# Micro_M3.net
KiCad netlist of a schematic drawn in Altium Designer
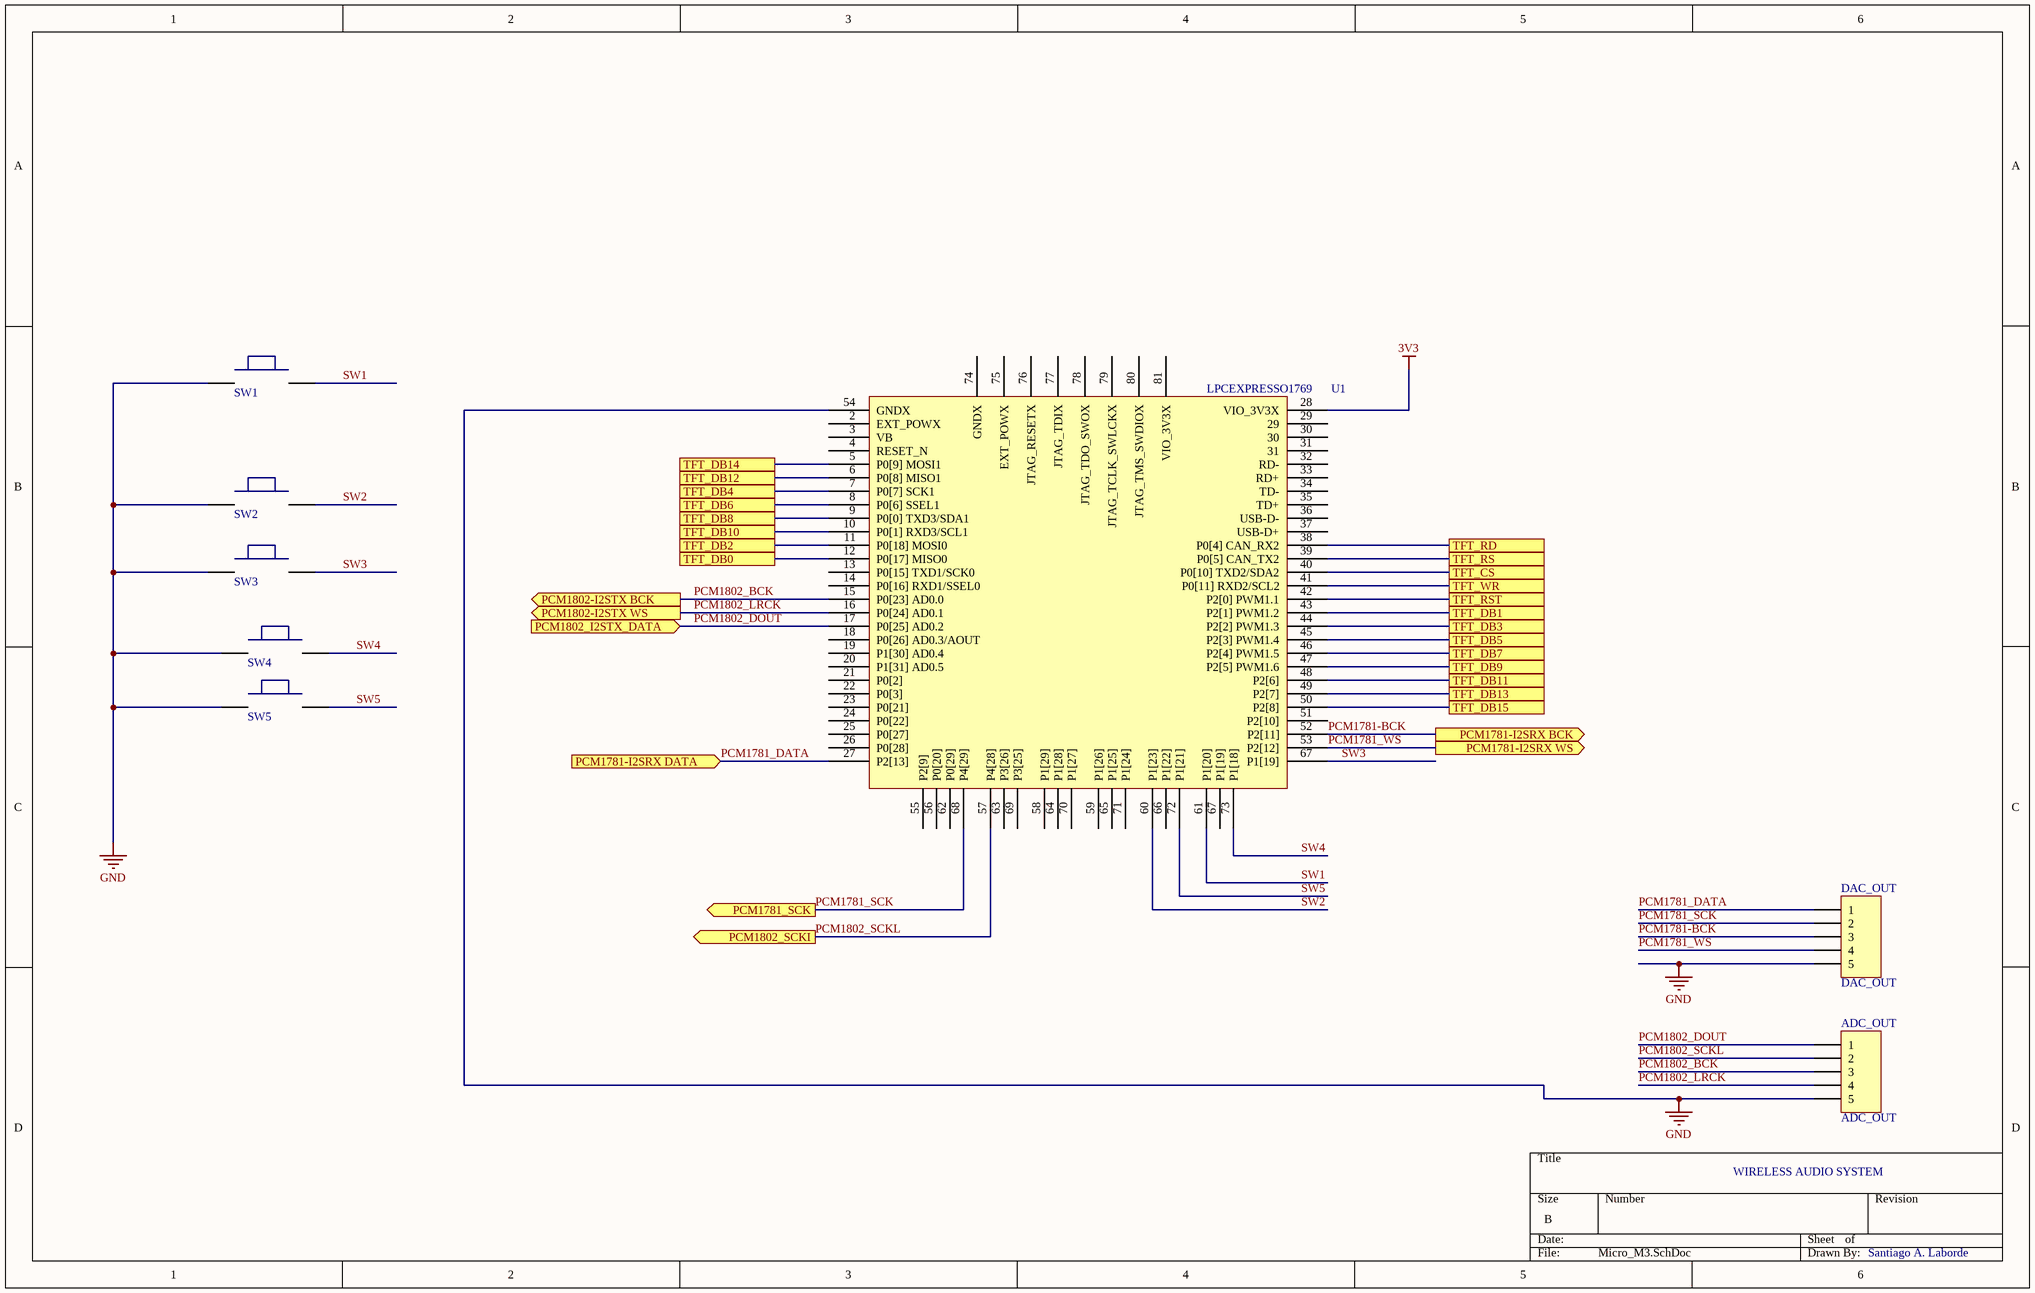
[diagram p0: Micro_M3.SchDoc]

(export (version "E")
  (design (tool "Eeschema 10.0.6"))
  (components
    (comp (ref "ADC_OUT")
      (value "ADC_OUT")
      (footprint "HDR1X5")
      (description "Header, 5-Pin")
      (fields (field (name "PUBLISHER") "Altium Limited"))
      (libsource (lib "Miscellaneous Connectors") (part "Header 5"))
    )
    (comp (ref "DAC_OUT")
      (value "DAC_OUT")
      (footprint "HDR1X5")
      (description "Header, 5-Pin")
      (fields (field (name "PUBLISHER") "Altium Limited"))
      (libsource (lib "Miscellaneous Connectors") (part "Header 5"))
    )
    (comp (ref "SW1")
      (value "PULSADOR")
      (footprint "Pulsador")
      (libsource (lib "TD2_Project") (part "PULSADOR"))
    )
    (comp (ref "SW2")
      (value "PULSADOR")
      (footprint "Pulsador")
      (libsource (lib "TD2_Project") (part "PULSADOR"))
    )
    (comp (ref "SW3")
      (value "PULSADOR")
      (footprint "Pulsador")
      (libsource (lib "TD2_Project") (part "PULSADOR"))
    )
    (comp (ref "SW4")
      (value "PULSADOR")
      (footprint "Pulsador")
      (libsource (lib "TD2_Project") (part "PULSADOR"))
    )
    (comp (ref "SW5")
      (value "PULSADOR")
      (footprint "SW_SMD(2)")
      (libsource (lib "TD2_Project") (part "PULSADOR"))
    )
    (comp (ref "U1")
      (value "LPCEXPRESSO1769")
      (footprint "LPCEXPRESSO1769")
      (libsource (lib "PCM") (part "LPCEXPRESSO1769"))
    )
  )
  (nets
    (net (code "1") (name "/PCM1781-BCK") (class "Default")
      (node (ref "DAC_OUT") (pin "3") (pinfunction "3_3") (pintype "passive"))
      (node (ref "U1") (pin "52") (pinfunction "P2[11]_52") (pintype "passive"))
    )
    (net (code "2") (name "/PCM1781_DATA") (class "Default")
      (node (ref "DAC_OUT") (pin "1") (pinfunction "1_1") (pintype "passive"))
      (node (ref "U1") (pin "27") (pinfunction "P2[13]_27") (pintype "passive"))
    )
    (net (code "3") (name "/PCM1781_SCK") (class "Default")
      (node (ref "DAC_OUT") (pin "2") (pinfunction "2_2") (pintype "passive"))
      (node (ref "U1") (pin "68") (pinfunction "P4[29]_68") (pintype "passive"))
    )
    (net (code "4") (name "/PCM1781_WS") (class "Default")
      (node (ref "DAC_OUT") (pin "4") (pinfunction "4_4") (pintype "passive"))
      (node (ref "U1") (pin "53") (pinfunction "P2[12]_53") (pintype "passive"))
    )
    (net (code "5") (name "/PCM1802_BCK") (class "Default")
      (node (ref "ADC_OUT") (pin "3") (pinfunction "3_3") (pintype "passive"))
      (node (ref "U1") (pin "15") (pinfunction "P0[23]_AD0.0_15") (pintype "passive"))
    )
    (net (code "6") (name "/PCM1802_DOUT") (class "Default")
      (node (ref "ADC_OUT") (pin "1") (pinfunction "1_1") (pintype "passive"))
      (node (ref "U1") (pin "17") (pinfunction "P0[25]_AD0.2_17") (pintype "passive"))
    )
    (net (code "7") (name "/PCM1802_LRCK") (class "Default")
      (node (ref "ADC_OUT") (pin "4") (pinfunction "4_4") (pintype "passive"))
      (node (ref "U1") (pin "16") (pinfunction "P0[24]_AD0.1_16") (pintype "passive"))
    )
    (net (code "8") (name "/PCM1802_SCKL") (class "Default")
      (node (ref "ADC_OUT") (pin "2") (pinfunction "2_2") (pintype "passive"))
      (node (ref "U1") (pin "57") (pinfunction "P4[28]_57") (pintype "passive"))
    )
    (net (code "9") (name "/SW1") (class "Default")
      (node (ref "SW1") (pin "2") (pintype "passive"))
      (node (ref "U1") (pin "61") (pinfunction "P1[20]_61") (pintype "passive"))
    )
    (net (code "10") (name "/SW2") (class "Default")
      (node (ref "SW2") (pin "2") (pintype "passive"))
      (node (ref "U1") (pin "60") (pinfunction "P1[23]_60") (pintype "passive"))
    )
    (net (code "11") (name "/SW3") (class "Default")
      (node (ref "SW3") (pin "2") (pintype "passive"))
      (node (ref "U1") (pin "67") (pinfunction "P1[19]_67") (pintype "passive"))
    )
    (net (code "12") (name "/SW4") (class "Default")
      (node (ref "SW4") (pin "2") (pintype "passive"))
      (node (ref "U1") (pin "73") (pinfunction "P1[18]_73") (pintype "passive"))
    )
    (net (code "13") (name "/SW5") (class "Default")
      (node (ref "SW5") (pin "2") (pintype "passive"))
      (node (ref "U1") (pin "72") (pinfunction "P1[21]_72") (pintype "passive"))
    )
    (net (code "14") (name "/TFT_CS") (class "Default")
      (node (ref "U1") (pin "40") (pinfunction "P0[10]_TXD2/SDA2_40") (pintype "passive"))
    )
    (net (code "15") (name "/TFT_DB0") (class "Default")
      (node (ref "U1") (pin "12") (pinfunction "P0[17]_MISO0_12") (pintype "passive"))
    )
    (net (code "16") (name "/TFT_DB1") (class "Default")
      (node (ref "U1") (pin "43") (pinfunction "P2[1]_PWM1.2_43") (pintype "passive"))
    )
    (net (code "17") (name "/TFT_DB2") (class "Default")
      (node (ref "U1") (pin "11") (pinfunction "P0[18]_MOSI0_11") (pintype "passive"))
    )
    (net (code "18") (name "/TFT_DB3") (class "Default")
      (node (ref "U1") (pin "44") (pinfunction "P2[2]_PWM1.3_44") (pintype "passive"))
    )
    (net (code "19") (name "/TFT_DB4") (class "Default")
      (node (ref "U1") (pin "7") (pinfunction "P0[7]_SCK1_7") (pintype "passive"))
    )
    (net (code "20") (name "/TFT_DB5") (class "Default")
      (node (ref "U1") (pin "45") (pinfunction "P2[3]_PWM1.4_45") (pintype "passive"))
    )
    (net (code "21") (name "/TFT_DB6") (class "Default")
      (node (ref "U1") (pin "8") (pinfunction "P0[6]_SSEL1_8") (pintype "passive"))
    )
    (net (code "22") (name "/TFT_DB7") (class "Default")
      (node (ref "U1") (pin "46") (pinfunction "P2[4]_PWM1.5_46") (pintype "passive"))
    )
    (net (code "23") (name "/TFT_DB8") (class "Default")
      (node (ref "U1") (pin "9") (pinfunction "P0[0]_TXD3/SDA1_9") (pintype "passive"))
    )
    (net (code "24") (name "/TFT_DB9") (class "Default")
      (node (ref "U1") (pin "47") (pinfunction "P2[5]_PWM1.6_47") (pintype "passive"))
    )
    (net (code "25") (name "/TFT_DB10") (class "Default")
      (node (ref "U1") (pin "10") (pinfunction "P0[1]_RXD3/SCL1_10") (pintype "passive"))
    )
    (net (code "26") (name "/TFT_DB11") (class "Default")
      (node (ref "U1") (pin "48") (pinfunction "P2[6]_48") (pintype "passive"))
    )
    (net (code "27") (name "/TFT_DB12") (class "Default")
      (node (ref "U1") (pin "6") (pinfunction "P0[8]_MISO1_6") (pintype "passive"))
    )
    (net (code "28") (name "/TFT_DB13") (class "Default")
      (node (ref "U1") (pin "49") (pinfunction "P2[7]_49") (pintype "passive"))
    )
    (net (code "29") (name "/TFT_DB14") (class "Default")
      (node (ref "U1") (pin "5") (pinfunction "P0[9]_MOSI1_5") (pintype "passive"))
    )
    (net (code "30") (name "/TFT_DB15") (class "Default")
      (node (ref "U1") (pin "50") (pinfunction "P2[8]_50") (pintype "passive"))
    )
    (net (code "31") (name "/TFT_RD") (class "Default")
      (node (ref "U1") (pin "38") (pinfunction "P0[4]_CAN_RX2_38") (pintype "passive"))
    )
    (net (code "32") (name "/TFT_RS") (class "Default")
      (node (ref "U1") (pin "39") (pinfunction "P0[5]_CAN_TX2_39") (pintype "passive"))
    )
    (net (code "33") (name "/TFT_RST") (class "Default")
      (node (ref "U1") (pin "42") (pinfunction "P2[0]_PWM1.1_42") (pintype "passive"))
    )
    (net (code "34") (name "/TFT_WR") (class "Default")
      (node (ref "U1") (pin "41") (pinfunction "P0[11]_RXD2/SCL2_41") (pintype "passive"))
    )
    (net (code "35") (name "3V3") (class "Default")
      (node (ref "U1") (pin "28") (pinfunction "VIO_3V3X_28") (pintype "passive"))
    )
    (net (code "36") (name "GND") (class "Default")
      (node (ref "ADC_OUT") (pin "5") (pinfunction "5_5") (pintype "passive"))
      (node (ref "DAC_OUT") (pin "5") (pinfunction "5_5") (pintype "passive"))
      (node (ref "SW1") (pin "1") (pintype "passive"))
      (node (ref "SW2") (pin "1") (pintype "passive"))
      (node (ref "SW3") (pin "1") (pintype "passive"))
      (node (ref "SW4") (pin "1") (pintype "passive"))
      (node (ref "SW5") (pin "1") (pintype "passive"))
      (node (ref "U1") (pin "54") (pinfunction "GNDX_54") (pintype "passive"))
    )
    (net (code "37") (name "unconnected-(U1-EXT_POWX-Pad2)") (class "Default")
      (node (ref "U1") (pin "2") (pinfunction "EXT_POWX_2") (pintype "passive"))
    )
    (net (code "38") (name "unconnected-(U1-EXT_POWX-Pad75)") (class "Default")
      (node (ref "U1") (pin "75") (pinfunction "EXT_POWX_75") (pintype "passive"))
    )
    (net (code "39") (name "unconnected-(U1-GNDX-Pad74)") (class "Default")
      (node (ref "U1") (pin "74") (pinfunction "GNDX_74") (pintype "passive"))
    )
    (net (code "40") (name "unconnected-(U1-JTAG_RESETX-Pad76)") (class "Default")
      (node (ref "U1") (pin "76") (pinfunction "JTAG_RESETX_76") (pintype "passive"))
    )
    (net (code "41") (name "unconnected-(U1-JTAG_TCLK_SWLCKX-Pad79)") (class "Default")
      (node (ref "U1") (pin "79") (pinfunction "JTAG_TCLK_SWLCKX_79") (pintype "passive"))
    )
    (net (code "42") (name "unconnected-(U1-JTAG_TDIX-Pad77)") (class "Default")
      (node (ref "U1") (pin "77") (pinfunction "JTAG_TDIX_77") (pintype "passive"))
    )
    (net (code "43") (name "unconnected-(U1-JTAG_TDO_SWOX-Pad78)") (class "Default")
      (node (ref "U1") (pin "78") (pinfunction "JTAG_TDO_SWOX_78") (pintype "passive"))
    )
    (net (code "44") (name "unconnected-(U1-JTAG_TMS_SWDIOX-Pad80)") (class "Default")
      (node (ref "U1") (pin "80") (pinfunction "JTAG_TMS_SWDIOX_80") (pintype "passive"))
    )
    (net (code "45") (name "unconnected-(U1-P0[2]-Pad21)") (class "Default")
      (node (ref "U1") (pin "21") (pinfunction "P0[2]_21") (pintype "passive"))
    )
    (net (code "46") (name "unconnected-(U1-P0[3]-Pad22)") (class "Default")
      (node (ref "U1") (pin "22") (pinfunction "P0[3]_22") (pintype "passive"))
    )
    (net (code "47") (name "unconnected-(U1-P0[15]_TXD1{slash}SCK0-Pad13)") (class "Default")
      (node (ref "U1") (pin "13") (pinfunction "P0[15]_TXD1/SCK0_13") (pintype "passive"))
    )
    (net (code "48") (name "unconnected-(U1-P0[16]_RXD1{slash}SSEL0-Pad14)") (class "Default")
      (node (ref "U1") (pin "14") (pinfunction "P0[16]_RXD1/SSEL0_14") (pintype "passive"))
    )
    (net (code "49") (name "unconnected-(U1-P0[20]-Pad56)") (class "Default")
      (node (ref "U1") (pin "56") (pinfunction "P0[20]_56") (pintype "passive"))
    )
    (net (code "50") (name "unconnected-(U1-P0[21]-Pad23)") (class "Default")
      (node (ref "U1") (pin "23") (pinfunction "P0[21]_23") (pintype "passive"))
    )
    (net (code "51") (name "unconnected-(U1-P0[22]-Pad24)") (class "Default")
      (node (ref "U1") (pin "24") (pinfunction "P0[22]_24") (pintype "passive"))
    )
    (net (code "52") (name "unconnected-(U1-P0[26]_AD0.3{slash}AOUT-Pad18)") (class "Default")
      (node (ref "U1") (pin "18") (pinfunction "P0[26]_AD0.3/AOUT_18") (pintype "passive"))
    )
    (net (code "53") (name "unconnected-(U1-P0[27]-Pad25)") (class "Default")
      (node (ref "U1") (pin "25") (pinfunction "P0[27]_25") (pintype "passive"))
    )
    (net (code "54") (name "unconnected-(U1-P0[28]-Pad26)") (class "Default")
      (node (ref "U1") (pin "26") (pinfunction "P0[28]_26") (pintype "passive"))
    )
    (net (code "55") (name "unconnected-(U1-P0[29]-Pad62)") (class "Default")
      (node (ref "U1") (pin "62") (pinfunction "P0[29]_62") (pintype "passive"))
    )
    (net (code "56") (name "unconnected-(U1-P1[19]-Pad67)") (class "Default")
      (node (ref "U1") (pin "67") (pinfunction "P1[19]_67") (pintype "passive"))
    )
    (net (code "57") (name "unconnected-(U1-P1[22]-Pad66)") (class "Default")
      (node (ref "U1") (pin "66") (pinfunction "P1[22]_66") (pintype "passive"))
    )
    (net (code "58") (name "unconnected-(U1-P1[24]-Pad71)") (class "Default")
      (node (ref "U1") (pin "71") (pinfunction "P1[24]_71") (pintype "passive"))
    )
    (net (code "59") (name "unconnected-(U1-P1[25]-Pad65)") (class "Default")
      (node (ref "U1") (pin "65") (pinfunction "P1[25]_65") (pintype "passive"))
    )
    (net (code "60") (name "unconnected-(U1-P1[26]-Pad59)") (class "Default")
      (node (ref "U1") (pin "59") (pinfunction "P1[26]_59") (pintype "passive"))
    )
    (net (code "61") (name "unconnected-(U1-P1[27]-Pad70)") (class "Default")
      (node (ref "U1") (pin "70") (pinfunction "P1[27]_70") (pintype "passive"))
    )
    (net (code "62") (name "unconnected-(U1-P1[28]-Pad64)") (class "Default")
      (node (ref "U1") (pin "64") (pinfunction "P1[28]_64") (pintype "passive"))
    )
    (net (code "63") (name "unconnected-(U1-P1[29]-Pad58)") (class "Default")
      (node (ref "U1") (pin "58") (pinfunction "P1[29]_58") (pintype "passive"))
    )
    (net (code "64") (name "unconnected-(U1-P1[30]_AD0.4-Pad19)") (class "Default")
      (node (ref "U1") (pin "19") (pinfunction "P1[30]_AD0.4_19") (pintype "passive"))
    )
    (net (code "65") (name "unconnected-(U1-P1[31]_AD0.5-Pad20)") (class "Default")
      (node (ref "U1") (pin "20") (pinfunction "P1[31]_AD0.5_20") (pintype "passive"))
    )
    (net (code "66") (name "unconnected-(U1-P2[9]-Pad55)") (class "Default")
      (node (ref "U1") (pin "55") (pinfunction "P2[9]_55") (pintype "passive"))
    )
    (net (code "67") (name "unconnected-(U1-P2[10]-Pad51)") (class "Default")
      (node (ref "U1") (pin "51") (pinfunction "P2[10]_51") (pintype "passive"))
    )
    (net (code "68") (name "unconnected-(U1-P3[25]-Pad69)") (class "Default")
      (node (ref "U1") (pin "69") (pinfunction "P3[25]_69") (pintype "passive"))
    )
    (net (code "69") (name "unconnected-(U1-P3[26]-Pad63)") (class "Default")
      (node (ref "U1") (pin "63") (pinfunction "P3[26]_63") (pintype "passive"))
    )
    (net (code "70") (name "unconnected-(U1-Pad29)") (class "Default")
      (node (ref "U1") (pin "29") (pinfunction "29_29") (pintype "passive"))
    )
    (net (code "71") (name "unconnected-(U1-Pad30)") (class "Default")
      (node (ref "U1") (pin "30") (pinfunction "30_30") (pintype "passive"))
    )
    (net (code "72") (name "unconnected-(U1-Pad31)") (class "Default")
      (node (ref "U1") (pin "31") (pinfunction "31_31") (pintype "passive"))
    )
    (net (code "73") (name "unconnected-(U1-RD+-Pad33)") (class "Default")
      (node (ref "U1") (pin "33") (pinfunction "RD+_33") (pintype "passive"))
    )
    (net (code "74") (name "unconnected-(U1-RD--Pad32)") (class "Default")
      (node (ref "U1") (pin "32") (pinfunction "RD-_32") (pintype "passive"))
    )
    (net (code "75") (name "unconnected-(U1-RESET_N-Pad4)") (class "Default")
      (node (ref "U1") (pin "4") (pinfunction "RESET_N_4") (pintype "passive"))
    )
    (net (code "76") (name "unconnected-(U1-TD+-Pad35)") (class "Default")
      (node (ref "U1") (pin "35") (pinfunction "TD+_35") (pintype "passive"))
    )
    (net (code "77") (name "unconnected-(U1-TD--Pad34)") (class "Default")
      (node (ref "U1") (pin "34") (pinfunction "TD-_34") (pintype "passive"))
    )
    (net (code "78") (name "unconnected-(U1-USB-D+-Pad37)") (class "Default")
      (node (ref "U1") (pin "37") (pinfunction "USB-D+_37") (pintype "passive"))
    )
    (net (code "79") (name "unconnected-(U1-USB-D--Pad36)") (class "Default")
      (node (ref "U1") (pin "36") (pinfunction "USB-D-_36") (pintype "passive"))
    )
    (net (code "80") (name "unconnected-(U1-VB-Pad3)") (class "Default")
      (node (ref "U1") (pin "3") (pinfunction "VB_3") (pintype "passive"))
    )
    (net (code "81") (name "unconnected-(U1-VIO_3V3X-Pad81)") (class "Default")
      (node (ref "U1") (pin "81") (pinfunction "VIO_3V3X_81") (pintype "passive"))
    )
  )
)
